# Netzteil_CA1.net
KiCad netlist of a schematic drawn in EAGLE
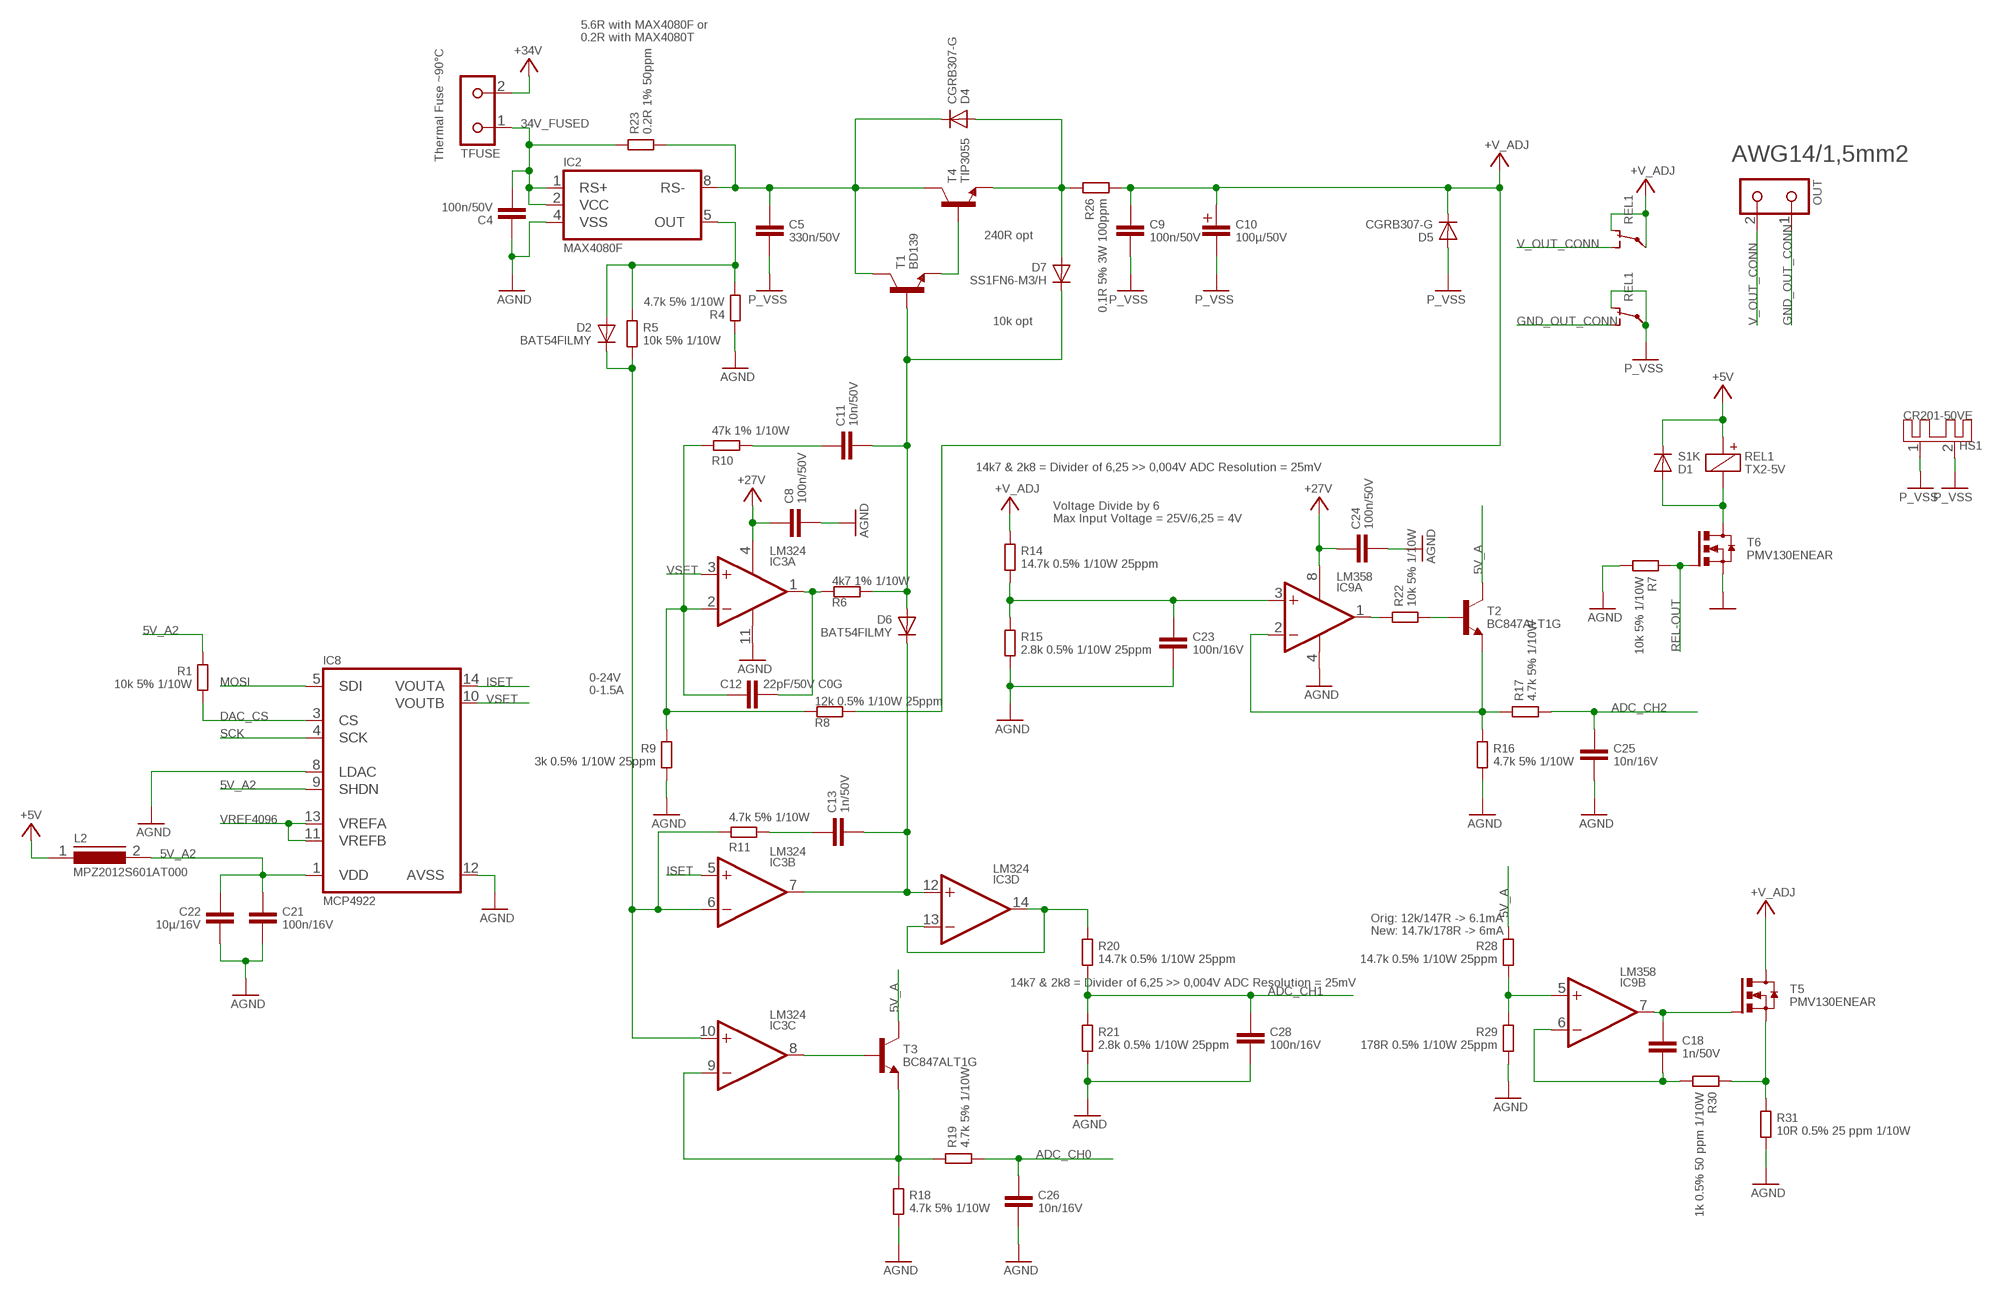
[diagram p0: schematic, sheet 1]
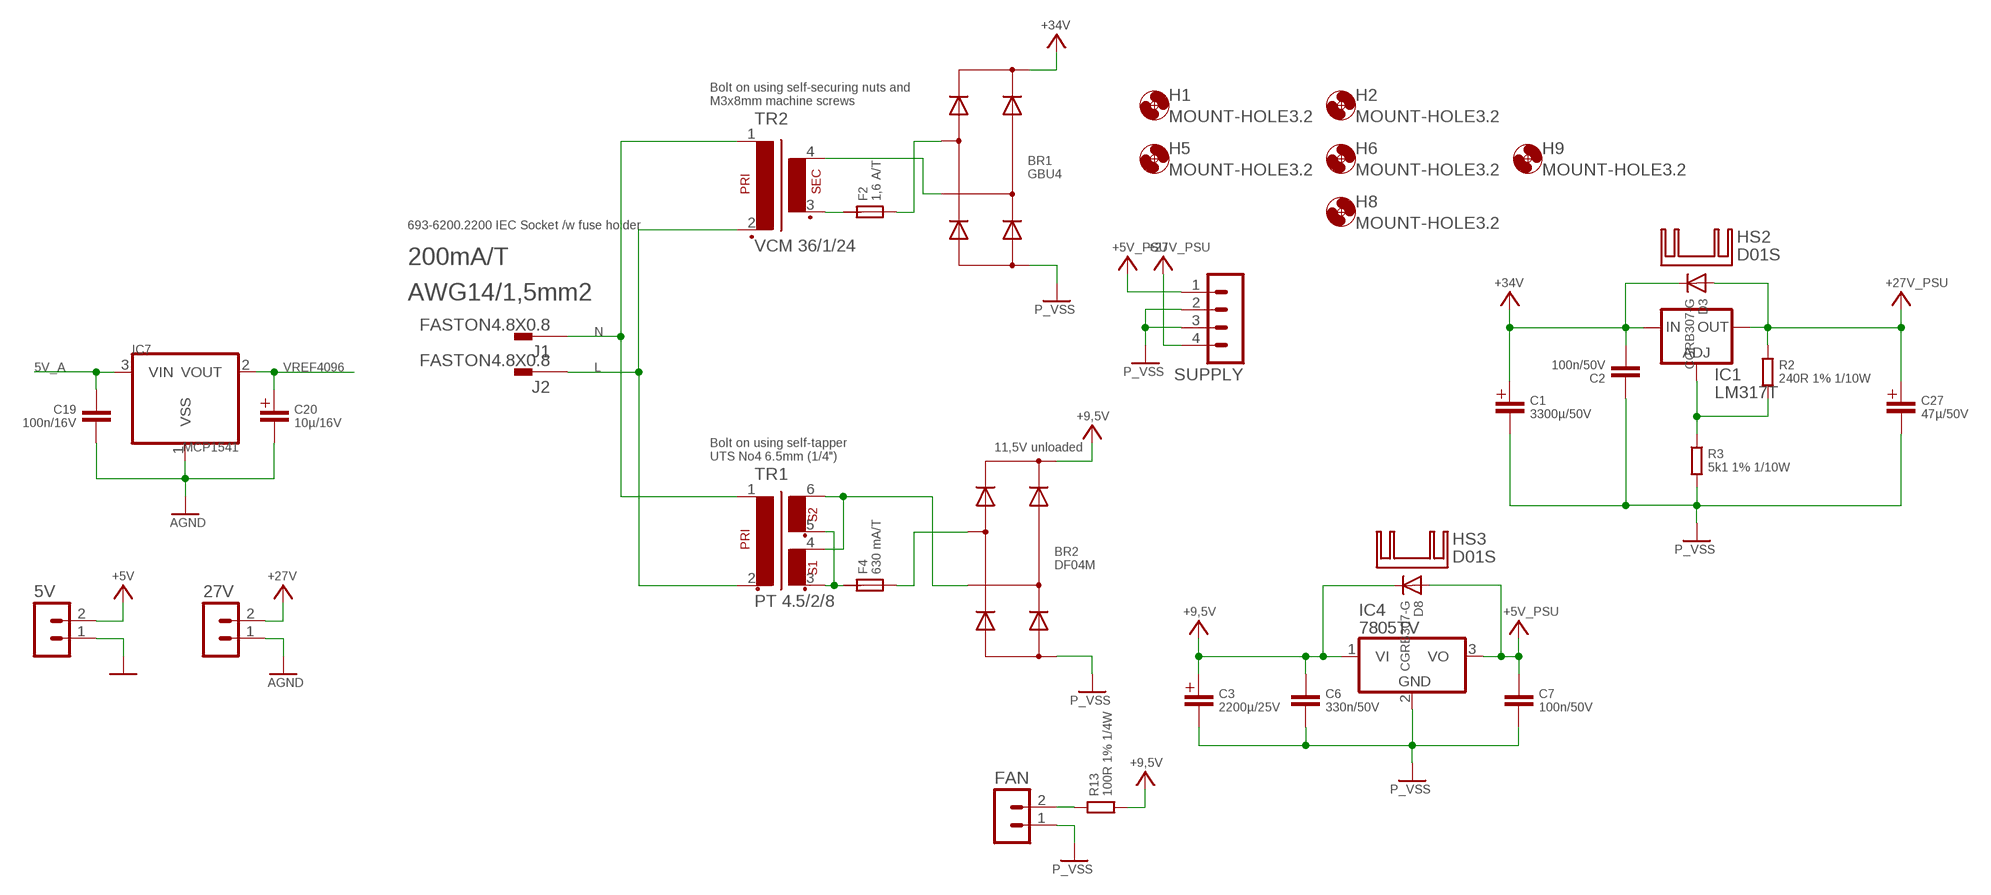
[diagram p1: schematic, sheet 2]
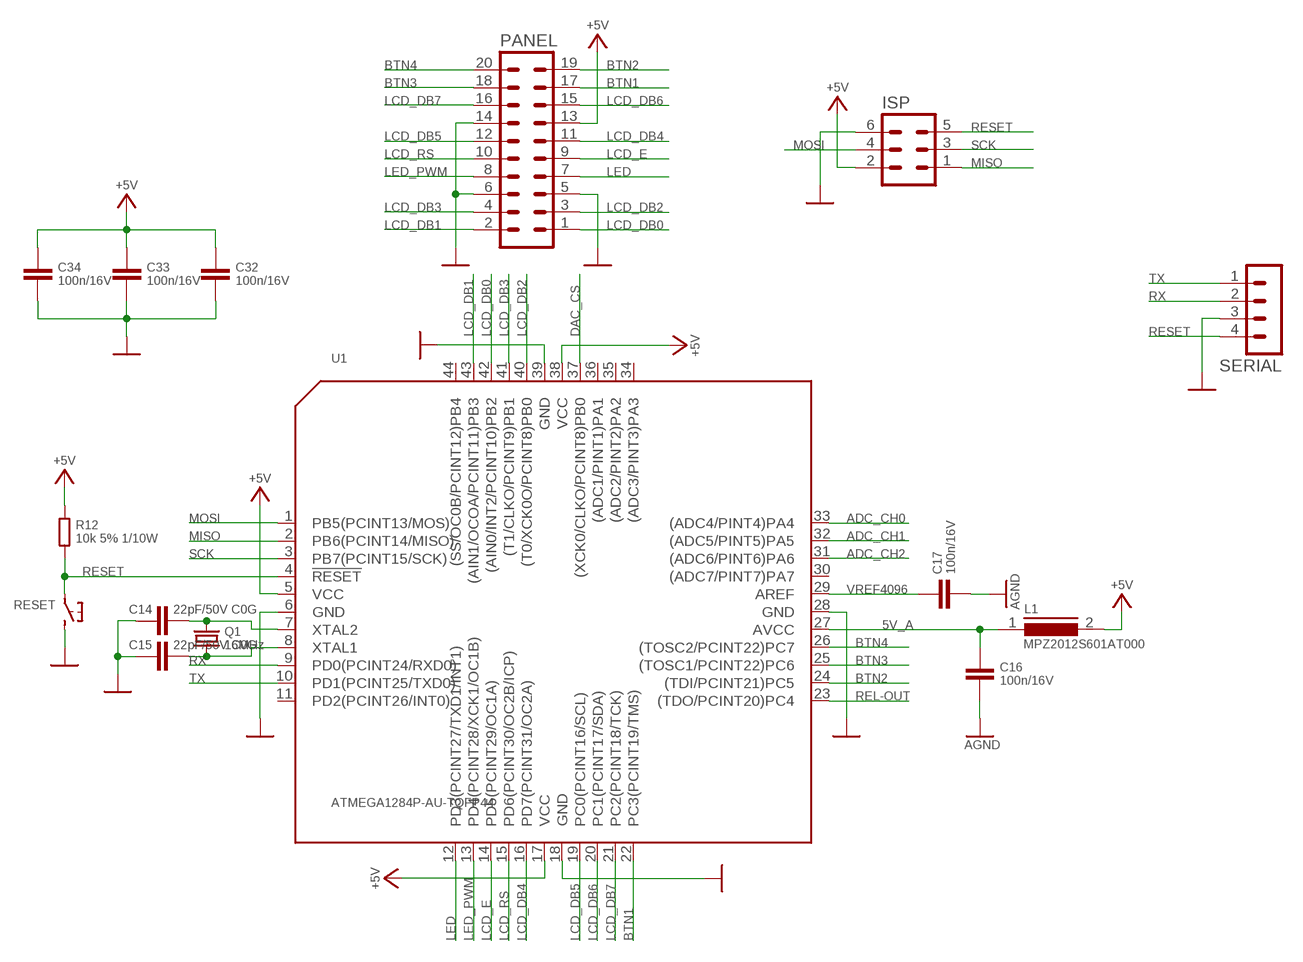
[diagram p2: schematic, sheet 3]

(export (version "E")
  (design (tool "Eeschema 10.0.6"))
  (components
    (comp (ref "C14")
      (value "22pF/50V C0G")
      (footprint "eagle-import:0805")
      (libsource (lib "eagle-import") (part "CC/0805"))
    )
    (comp (ref "C15")
      (value "22pF/50V C0G")
      (footprint "eagle-import:0805")
      (libsource (lib "eagle-import") (part "CC/0805"))
    )
    (comp (ref "C16")
      (value "100n/16V")
      (footprint "eagle-import:0805")
      (libsource (lib "eagle-import") (part "CC/0805"))
    )
    (comp (ref "C17")
      (value "100n/16V")
      (footprint "eagle-import:0805")
      (libsource (lib "eagle-import") (part "CC/0805"))
    )
    (comp (ref "C32")
      (value "100n/16V")
      (footprint "eagle-import:0805")
      (libsource (lib "eagle-import") (part "CC/0805"))
    )
    (comp (ref "C33")
      (value "100n/16V")
      (footprint "eagle-import:0805")
      (libsource (lib "eagle-import") (part "CC/0805"))
    )
    (comp (ref "C34")
      (value "100n/16V")
      (footprint "eagle-import:0805")
      (libsource (lib "eagle-import") (part "CC/0805"))
    )
    (comp (ref "ISP")
      (value "ML6")
      (footprint "eagle-import:ML6")
      (libsource (lib "eagle-import") (part "ML6"))
    )
    (comp (ref "L1")
      (value "MPZ2012S601AT000")
      (footprint "eagle-import:C0805K")
      (libsource (lib "eagle-import") (part "L0805"))
    )
    (comp (ref "PANEL")
      (value "MA10-2")
      (footprint "eagle-import:MA10-2")
      (libsource (lib "eagle-import") (part "MA10-2"))
    )
    (comp (ref "Q1")
      (value "16MHz")
      (footprint "eagle-import:Q-5X3.2MM-TXC-7A.SERIES")
      (libsource (lib "eagle-import") (part "Q5X3.2MM-TXC-7A-SERIES"))
    )
    (comp (ref "R12")
      (value "10k 5% 1/10W")
      (footprint "eagle-import:C0805K")
      (libsource (lib "eagle-import") (part "R-SMD0805"))
    )
    (comp (ref "RESET")
      (value "TS1B3F-10XX")
      (footprint "eagle-import:B3F-10XX")
      (libsource (lib "eagle-import") (part "TS1B3F-10XX"))
    )
    (comp (ref "SERIAL")
      (value "MA04-1")
      (footprint "eagle-import:MA04-1")
      (libsource (lib "eagle-import") (part "MA04-1"))
    )
    (comp (ref "U1")
      (value "ATMEGA1284P-AU-TQFP44")
      (footprint "eagle-import:TQFP44-0.8-9.6X9.6MM")
      (fields (field (name "MPN") "ATMEGA1284P-AU"))
      (libsource (lib "eagle-import") (part "MCU-ATMEGA1284P-AU(TQFP44)"))
    )
    (comp (ref "C4")
      (value "100n/50V")
      (footprint "eagle-import:0805")
      (libsource (lib "eagle-import") (part "CC/0805"))
    )
    (comp (ref "C5")
      (value "330n/50V")
      (footprint "eagle-import:0805")
      (libsource (lib "eagle-import") (part "CC/0805"))
    )
    (comp (ref "C8")
      (value "100n/50V")
      (footprint "eagle-import:0805")
      (libsource (lib "eagle-import") (part "CC/0805"))
    )
    (comp (ref "C9")
      (value "100n/50V")
      (footprint "eagle-import:0805")
      (libsource (lib "eagle-import") (part "CC/0805"))
    )
    (comp (ref "C10")
      (value "100µ/50V")
      (footprint "eagle-import:C+_3.5_8")
      (libsource (lib "eagle-import") (part "C+3.5/8"))
    )
    (comp (ref "C11")
      (value "10n/50V")
      (footprint "eagle-import:0805")
      (libsource (lib "eagle-import") (part "CC/0805"))
    )
    (comp (ref "C12")
      (value "22pF/50V C0G")
      (footprint "eagle-import:0805")
      (libsource (lib "eagle-import") (part "CC/0805"))
    )
    (comp (ref "C13")
      (value "1n/50V")
      (footprint "eagle-import:0805")
      (libsource (lib "eagle-import") (part "CC/0805"))
    )
    (comp (ref "C18")
      (value "1n/50V")
      (footprint "eagle-import:0805")
      (libsource (lib "eagle-import") (part "CC/0805"))
    )
    (comp (ref "C21")
      (value "100n/16V")
      (footprint "eagle-import:0805")
      (libsource (lib "eagle-import") (part "CC/0805"))
    )
    (comp (ref "C22")
      (value "10µ/16V")
      (footprint "eagle-import:1206")
      (libsource (lib "eagle-import") (part "CC/1206"))
    )
    (comp (ref "C23")
      (value "100n/16V")
      (footprint "eagle-import:0805")
      (libsource (lib "eagle-import") (part "CC/0805"))
    )
    (comp (ref "C24")
      (value "100n/50V")
      (footprint "eagle-import:0805")
      (libsource (lib "eagle-import") (part "CC/0805"))
    )
    (comp (ref "C25")
      (value "10n/16V")
      (footprint "eagle-import:0805")
      (libsource (lib "eagle-import") (part "CC/0805"))
    )
    (comp (ref "C26")
      (value "10n/16V")
      (footprint "eagle-import:0805")
      (libsource (lib "eagle-import") (part "CC/0805"))
    )
    (comp (ref "C28")
      (value "100n/16V")
      (footprint "eagle-import:0805")
      (libsource (lib "eagle-import") (part "CC/0805"))
    )
    (comp (ref "D1")
      (value "S1K")
      (footprint "eagle-import:DO214AC")
      (libsource (lib "eagle-import") (part "D"))
    )
    (comp (ref "D2")
      (value "BAT54FILMY")
      (footprint "eagle-import:SOT23")
      (libsource (lib "eagle-import") (part "DBAT54FILMY"))
    )
    (comp (ref "D4")
      (value "CGRB307-G")
      (footprint "eagle-import:DO214AA-CGRB307-G")
      (libsource (lib "eagle-import") (part "DWIDE"))
    )
    (comp (ref "D5")
      (value "CGRB307-G")
      (footprint "eagle-import:DO214AA-CGRB307-G")
      (libsource (lib "eagle-import") (part "DWIDE"))
    )
    (comp (ref "D6")
      (value "BAT54FILMY")
      (footprint "eagle-import:SOT23")
      (libsource (lib "eagle-import") (part "DBAT54FILMY"))
    )
    (comp (ref "D7")
      (value "SS1FN6-M3/H")
      (footprint "eagle-import:DO219AB-2")
      (libsource (lib "eagle-import") (part "DDO219AB-2"))
    )
    (comp (ref "HS1")
      (value "CR201-50VE")
      (footprint "eagle-import:CR201-50")
      (libsource (lib "eagle-import") (part "HSCR201-50"))
    )
    (comp (ref "IC2")
      (value "MAX4080F")
      (footprint "eagle-import:SOP8")
      (libsource (lib "eagle-import") (part "MAX4080"))
    )
    (comp (ref "IC3")
      (value "LM324")
      (footprint "eagle-import:SO14")
      (fields (field (name "OC_MOUSER") "595-LM324ADR"))
      (libsource (lib "eagle-import") (part "QUAD-OPVOPA4197"))
    )
    (comp (ref "IC8")
      (value "MCP4922")
      (footprint "eagle-import:TSSOP14")
      (libsource (lib "eagle-import") (part "MCP4922"))
    )
    (comp (ref "IC9")
      (value "LM358")
      (footprint "eagle-import:SOP8")
      (fields (field (name "OC_MOUSER") "595-LM358ADR"))
      (libsource (lib "eagle-import") (part "DUAL-OPVSOP8"))
    )
    (comp (ref "L2")
      (value "MPZ2012S601AT000")
      (footprint "eagle-import:C0805K")
      (libsource (lib "eagle-import") (part "L0805"))
    )
    (comp (ref "OUT")
      (value "KL2691311500002")
      (footprint "eagle-import:KL2-691311500002")
      (libsource (lib "eagle-import") (part "KL2691311500002"))
    )
    (comp (ref "R1")
      (value "10k 5% 1/10W")
      (footprint "eagle-import:C0805K")
      (libsource (lib "eagle-import") (part "R-SMD0805"))
    )
    (comp (ref "R4")
      (value "4.7k 5% 1/10W")
      (footprint "eagle-import:C0805K")
      (libsource (lib "eagle-import") (part "R-SMD0805"))
    )
    (comp (ref "R5")
      (value "10k 5% 1/10W")
      (footprint "eagle-import:C0805K")
      (libsource (lib "eagle-import") (part "R-SMD0805"))
    )
    (comp (ref "R6")
      (value "4k7 1% 1/10W")
      (footprint "eagle-import:C0805K")
      (libsource (lib "eagle-import") (part "R-SMD0805"))
    )
    (comp (ref "R7")
      (value "10k 5% 1/10W")
      (footprint "eagle-import:C0805K")
      (libsource (lib "eagle-import") (part "R-SMD0805"))
    )
    (comp (ref "R8")
      (value "12k 0.5% 1/10W 25ppm")
      (footprint "eagle-import:C0805K")
      (libsource (lib "eagle-import") (part "R-SMD0805"))
    )
    (comp (ref "R9")
      (value "3k 0.5% 1/10W 25ppm")
      (footprint "eagle-import:C0805K")
      (libsource (lib "eagle-import") (part "R-SMD0805"))
    )
    (comp (ref "R10")
      (value "47k 1% 1/10W")
      (footprint "eagle-import:C0805K")
      (libsource (lib "eagle-import") (part "R-SMD0805"))
    )
    (comp (ref "R11")
      (value "4.7k 5% 1/10W")
      (footprint "eagle-import:C0805K")
      (libsource (lib "eagle-import") (part "R-SMD0805"))
    )
    (comp (ref "R14")
      (value "14.7k 0.5% 1/10W 25ppm")
      (footprint "eagle-import:C0805K")
      (libsource (lib "eagle-import") (part "R-SMD0805"))
    )
    (comp (ref "R15")
      (value "2.8k 0.5% 1/10W 25ppm")
      (footprint "eagle-import:C0805K")
      (libsource (lib "eagle-import") (part "R-SMD0805"))
    )
    (comp (ref "R16")
      (value "4.7k 5% 1/10W")
      (footprint "eagle-import:C0805K")
      (libsource (lib "eagle-import") (part "R-SMD0805"))
    )
    (comp (ref "R17")
      (value "4.7k 5% 1/10W")
      (footprint "eagle-import:C0805K")
      (libsource (lib "eagle-import") (part "R-SMD0805"))
    )
    (comp (ref "R18")
      (value "4.7k 5% 1/10W")
      (footprint "eagle-import:C0805K")
      (libsource (lib "eagle-import") (part "R-SMD0805"))
    )
    (comp (ref "R19")
      (value "4.7k 5% 1/10W")
      (footprint "eagle-import:C0805K")
      (libsource (lib "eagle-import") (part "R-SMD0805"))
    )
    (comp (ref "R20")
      (value "14.7k 0.5% 1/10W 25ppm")
      (footprint "eagle-import:C0805K")
      (libsource (lib "eagle-import") (part "R-SMD0805"))
    )
    (comp (ref "R21")
      (value "2.8k 0.5% 1/10W 25ppm")
      (footprint "eagle-import:C0805K")
      (libsource (lib "eagle-import") (part "R-SMD0805"))
    )
    (comp (ref "R22")
      (value "10k 5% 1/10W")
      (footprint "eagle-import:C0805K")
      (libsource (lib "eagle-import") (part "R-SMD0805"))
    )
    (comp (ref "R23")
      (value "0.2R 1% 50ppm")
      (footprint "eagle-import:LRMAP2512")
      (libsource (lib "eagle-import") (part "R-SMDLRMAP2512"))
    )
    (comp (ref "R26")
      (value "0.1R 5% 3W 100ppm")
      (footprint "eagle-import:YAG_PT2512")
      (libsource (lib "eagle-import") (part "R-SMD2512"))
    )
    (comp (ref "R28")
      (value "14.7k 0.5% 1/10W 25ppm")
      (footprint "eagle-import:C0805K")
      (libsource (lib "eagle-import") (part "R-SMD0805"))
    )
    (comp (ref "R29")
      (value "178R 0.5% 1/10W 25ppm")
      (footprint "eagle-import:C0805K")
      (libsource (lib "eagle-import") (part "R-SMD0805"))
    )
    (comp (ref "R30")
      (value "1k 0.5% 50 ppm 1/10W")
      (footprint "eagle-import:C0805K")
      (libsource (lib "eagle-import") (part "R-SMD0805"))
    )
    (comp (ref "R31")
      (value "10R 0.5% 25 ppm 1/10W")
      (footprint "eagle-import:C0805K")
      (libsource (lib "eagle-import") (part "R-SMD0805"))
    )
    (comp (ref "REL1")
      (value "TX2-5V")
      (footprint "eagle-import:REL-TX2")
      (fields (field (name "OC_MOUSER") "769-TX2-5V"))
      (libsource (lib "eagle-import") (part "REL-2UTX2"))
    )
    (comp (ref "T1")
      (value "BD139")
      (footprint "eagle-import:TO126")
      (libsource (lib "eagle-import") (part "T-NPNTO126-ECB"))
    )
    (comp (ref "T2")
      (value "BC847ALT1G")
      (footprint "eagle-import:SOT23-BEC")
      (libsource (lib "eagle-import") (part "T-NPNSOT23-BEC"))
    )
    (comp (ref "T3")
      (value "BC847ALT1G")
      (footprint "eagle-import:SOT23-BEC")
      (libsource (lib "eagle-import") (part "T-NPNSOT23-BEC"))
    )
    (comp (ref "T4")
      (value "TIP3055")
      (footprint "eagle-import:TOP3AV")
      (libsource (lib "eagle-import") (part "T-NPNTOP3AV-BCE"))
    )
    (comp (ref "T5")
      (value "PMV130ENEAR")
      (footprint "eagle-import:SOT23")
      (libsource (lib "eagle-import") (part "T-NMOSIRLML2502PBF"))
    )
    (comp (ref "T6")
      (value "PMV130ENEAR")
      (footprint "eagle-import:SOT23")
      (libsource (lib "eagle-import") (part "T-NMOSIRLML2502PBF"))
    )
    (comp (ref "TFUSE")
      (value "KL2691311500002")
      (footprint "eagle-import:KL2-691311500002")
      (libsource (lib "eagle-import") (part "KL2691311500002"))
    )
    (comp (ref "5V")
      (value "JST-PH-2.0-2P")
      (footprint "eagle-import:JST-PH-2.0-2P")
      (libsource (lib "eagle-import") (part "JST-PH-2.0-2P"))
    )
    (comp (ref "27V")
      (value "JST-PH-2.0-2P")
      (footprint "eagle-import:JST-PH-2.0-2P")
      (libsource (lib "eagle-import") (part "JST-PH-2.0-2P"))
    )
    (comp (ref "BR1")
      (value "GBU4")
      (footprint "eagle-import:GBU4S")
      (libsource (lib "eagle-import") (part "GBU8M"))
    )
    (comp (ref "BR2")
      (value "DF04M")
      (footprint "eagle-import:BR-DIL2")
      (libsource (lib "eagle-import") (part "BRDIL2"))
    )
    (comp (ref "C1")
      (value "3300µ/50V")
      (footprint "eagle-import:C+_7.5_18")
      (libsource (lib "eagle-import") (part "C+7.5/18"))
    )
    (comp (ref "C2")
      (value "100n/50V")
      (footprint "eagle-import:0805")
      (libsource (lib "eagle-import") (part "CC/0805"))
    )
    (comp (ref "C3")
      (value "2200µ/25V")
      (footprint "eagle-import:C+_5_12.5")
      (libsource (lib "eagle-import") (part "C+5/12.5"))
    )
    (comp (ref "C6")
      (value "330n/50V")
      (footprint "eagle-import:0805")
      (libsource (lib "eagle-import") (part "CC/0805"))
    )
    (comp (ref "C7")
      (value "100n/50V")
      (footprint "eagle-import:0805")
      (libsource (lib "eagle-import") (part "CC/0805"))
    )
    (comp (ref "C19")
      (value "100n/16V")
      (footprint "eagle-import:0805")
      (libsource (lib "eagle-import") (part "CC/0805"))
    )
    (comp (ref "C20")
      (value "10µ/16V")
      (footprint "eagle-import:C+_1.5_4")
      (libsource (lib "eagle-import") (part "C+1.5/4"))
    )
    (comp (ref "C27")
      (value "47µ/50V")
      (footprint "eagle-import:C+_2.5_6.3")
      (libsource (lib "eagle-import") (part "C+2.5/6.3"))
    )
    (comp (ref "D3")
      (value "CGRB307-G")
      (footprint "eagle-import:DO214AA-CGRB307-G")
      (libsource (lib "eagle-import") (part "DWIDE"))
    )
    (comp (ref "D8")
      (value "CGRB307-G")
      (footprint "eagle-import:DO214AA-CGRB307-G")
      (libsource (lib "eagle-import") (part "DWIDE"))
    )
    (comp (ref "F2")
      (value "1,6 A/T")
      (footprint "eagle-import:F5X20")
      (libsource (lib "eagle-import") (part "F5X20"))
    )
    (comp (ref "F4")
      (value "630 mA/T")
      (footprint "eagle-import:F5X20")
      (libsource (lib "eagle-import") (part "F5X20"))
    )
    (comp (ref "FAN")
      (value "JST-PH-2.0-2P")
      (footprint "eagle-import:JST-PH-2.0-2P")
      (libsource (lib "eagle-import") (part "JST-PH-2.0-2P"))
    )
    (comp (ref "H1")
      (value "MOUNT-HOLE3.2")
      (footprint "eagle-import:3,2")
      (libsource (lib "eagle-import") (part "MOUNT-HOLE3.2"))
    )
    (comp (ref "H2")
      (value "MOUNT-HOLE3.2")
      (footprint "eagle-import:3,2")
      (libsource (lib "eagle-import") (part "MOUNT-HOLE3.2"))
    )
    (comp (ref "H5")
      (value "MOUNT-HOLE3.2")
      (footprint "eagle-import:3,2")
      (libsource (lib "eagle-import") (part "MOUNT-HOLE3.2"))
    )
    (comp (ref "H6")
      (value "MOUNT-HOLE3.2")
      (footprint "eagle-import:3,2")
      (libsource (lib "eagle-import") (part "MOUNT-HOLE3.2"))
    )
    (comp (ref "H8")
      (value "MOUNT-HOLE3.2")
      (footprint "eagle-import:3,2")
      (libsource (lib "eagle-import") (part "MOUNT-HOLE3.2"))
    )
    (comp (ref "H9")
      (value "MOUNT-HOLE3.2")
      (footprint "eagle-import:3,2")
      (libsource (lib "eagle-import") (part "MOUNT-HOLE3.2"))
    )
    (comp (ref "HS2")
      (value "D01S")
      (footprint "eagle-import:D01S")
      (libsource (lib "eagle-import") (part "D01S"))
    )
    (comp (ref "HS3")
      (value "D01S")
      (footprint "eagle-import:D01S")
      (libsource (lib "eagle-import") (part "D01S"))
    )
    (comp (ref "IC1")
      (value "LM317T")
      (footprint "eagle-import:317TS")
      (libsource (lib "eagle-import") (part "LM317TS"))
    )
    (comp (ref "IC4")
      (value "7805TV")
      (footprint "eagle-import:TO220V")
      (libsource (lib "eagle-import") (part "78TV05"))
    )
    (comp (ref "IC7")
      (value "MCP1541")
      (footprint "eagle-import:TO92-G")
      (libsource (lib "eagle-import") (part "MCP1541"))
    )
    (comp (ref "J1")
      (value "FASTON4.8X0.8")
      (footprint "eagle-import:FASTON-4.8X0.8")
      (libsource (lib "eagle-import") (part "FASTON4.8X0.8"))
    )
    (comp (ref "J2")
      (value "FASTON4.8X0.8")
      (footprint "eagle-import:FASTON-4.8X0.8")
      (libsource (lib "eagle-import") (part "FASTON4.8X0.8"))
    )
    (comp (ref "R2")
      (value "240R 1% 1/10W")
      (footprint "eagle-import:C0805K")
      (libsource (lib "eagle-import") (part "R-SMD0805"))
    )
    (comp (ref "R3")
      (value "5k1 1% 1/10W")
      (footprint "eagle-import:C0805K")
      (libsource (lib "eagle-import") (part "R-SMD0805"))
    )
    (comp (ref "R13")
      (value "100R 1% 1/4W")
      (footprint "eagle-import:C0805K")
      (libsource (lib "eagle-import") (part "R-SMD0805"))
    )
    (comp (ref "SUPPLY")
      (value "JST-PH-2.0-4P")
      (footprint "eagle-import:JST-PH-2.0-4P")
      (libsource (lib "eagle-import") (part "JST-PH-2.0-4P"))
    )
    (comp (ref "TR1")
      (value "PT 4.5/2/8")
      (footprint "eagle-import:PT_4,5_2_..")
      (libsource (lib "eagle-import") (part "PT4,5/2/.."))
    )
    (comp (ref "TR2")
      (value "VCM 36/1/24")
      (footprint "eagle-import:VCM36_1_24")
      (libsource (lib "eagle-import") (part "VCM36/1/24"))
    )
  )
  (nets
    (net (code "1") (name "+5V") (class "Default")
      (node (ref "5V") (pin "2") (pinfunction "2_2") (pintype "passive"))
      (node (ref "C32") (pin "1") (pinfunction "1_1") (pintype "passive"))
      (node (ref "C33") (pin "1") (pinfunction "1_1") (pintype "passive"))
      (node (ref "C34") (pin "1") (pinfunction "1_1") (pintype "passive"))
      (node (ref "D1") (pin "C") (pinfunction "C_C") (pintype "passive"))
      (node (ref "ISP") (pin "2") (pinfunction "2_2") (pintype "passive"))
      (node (ref "L1") (pin "2") (pinfunction "2_2") (pintype "passive"))
      (node (ref "L2") (pin "1") (pinfunction "1_1") (pintype "passive"))
      (node (ref "PANEL") (pin "13") (pinfunction "13_13") (pintype "passive"))
      (node (ref "R12") (pin "1") (pinfunction "1_1") (pintype "passive"))
      (node (ref "REL1") (pin "+") (pinfunction "+_+") (pintype "passive"))
      (node (ref "U1") (pin "17") (pinfunction "VCC_17") (pintype "bidirectional"))
      (node (ref "U1") (pin "38") (pinfunction "VCC_38") (pintype "bidirectional"))
      (node (ref "U1") (pin "5") (pinfunction "VCC_5") (pintype "bidirectional"))
    )
    (net (code "2") (name "+5V_PSU") (class "Default")
      (node (ref "C7") (pin "1") (pinfunction "1_1") (pintype "passive"))
      (node (ref "D8") (pin "A") (pinfunction "A_A") (pintype "passive"))
      (node (ref "IC4") (pin "3") (pinfunction "VO_3") (pintype "passive"))
      (node (ref "SUPPLY") (pin "1") (pinfunction "1_1") (pintype "passive"))
    )
    (net (code "3") (name "+9,5V") (class "Default")
      (node (ref "BR2") (pin "DC+") (pinfunction "DC+_DC+") (pintype "passive"))
      (node (ref "C3") (pin "+") (pinfunction "+_+") (pintype "passive"))
      (node (ref "C6") (pin "1") (pinfunction "1_1") (pintype "passive"))
      (node (ref "D8") (pin "C") (pinfunction "C_C") (pintype "passive"))
      (node (ref "IC4") (pin "1") (pinfunction "VI_1") (pintype "input"))
      (node (ref "R13") (pin "2") (pinfunction "2_2") (pintype "passive"))
    )
    (net (code "4") (name "+27V") (class "Default")
      (node (ref "27V") (pin "2") (pinfunction "2_2") (pintype "passive"))
      (node (ref "C24") (pin "1") (pinfunction "1_1") (pintype "passive"))
      (node (ref "C8") (pin "1") (pinfunction "1_1") (pintype "passive"))
      (node (ref "IC3") (pin "4") (pinfunction "V+_4") (pintype "power_in"))
      (node (ref "IC9") (pin "8") (pinfunction "V+_8") (pintype "power_in"))
    )
    (net (code "5") (name "+27V_PSU") (class "Default")
      (node (ref "C27") (pin "+") (pinfunction "+_+") (pintype "passive"))
      (node (ref "D3") (pin "A") (pinfunction "A_A") (pintype "passive"))
      (node (ref "IC1") (pin "2") (pinfunction "OUT_2") (pintype "passive"))
      (node (ref "R2") (pin "1") (pinfunction "1_1") (pintype "passive"))
      (node (ref "SUPPLY") (pin "4") (pinfunction "4_4") (pintype "passive"))
    )
    (net (code "6") (name "+34V") (class "Default")
      (node (ref "BR1") (pin "+") (pinfunction "DC+_+") (pintype "passive"))
      (node (ref "C1") (pin "+") (pinfunction "+_+") (pintype "passive"))
      (node (ref "C2") (pin "2") (pinfunction "2_2") (pintype "passive"))
      (node (ref "D3") (pin "C") (pinfunction "C_C") (pintype "passive"))
      (node (ref "IC1") (pin "3") (pinfunction "IN_3") (pintype "input"))
      (node (ref "TFUSE") (pin "2") (pinfunction "2_2") (pintype "passive"))
    )
    (net (code "7") (name "+V_ADJ") (class "Default")
      (node (ref "C10") (pin "+") (pinfunction "+_+") (pintype "passive"))
      (node (ref "C9") (pin "1") (pinfunction "1_1") (pintype "passive"))
      (node (ref "D5") (pin "C") (pinfunction "C_C") (pintype "passive"))
      (node (ref "R14") (pin "1") (pinfunction "1_1") (pintype "passive"))
      (node (ref "R26") (pin "2") (pinfunction "2_2") (pintype "passive"))
      (node (ref "R8") (pin "1") (pinfunction "1_1") (pintype "passive"))
      (node (ref "REL1") (pin "O1") (pinfunction "O_O1") (pintype "passive"))
      (node (ref "REL1") (pin "P1") (pinfunction "P_P1") (pintype "passive"))
      (node (ref "T5") (pin "3") (pinfunction "D_3") (pintype "passive"))
    )
    (net (code "8") (name "5V_A") (class "Default")
      (node (ref "C16") (pin "1") (pinfunction "1_1") (pintype "passive"))
      (node (ref "C19") (pin "1") (pinfunction "1_1") (pintype "passive"))
      (node (ref "IC7") (pin "3") (pinfunction "VIN_3") (pintype "power_in"))
      (node (ref "L1") (pin "1") (pinfunction "1_1") (pintype "passive"))
      (node (ref "R28") (pin "1") (pinfunction "1_1") (pintype "passive"))
      (node (ref "T2") (pin "C") (pinfunction "C_C") (pintype "passive"))
      (node (ref "T3") (pin "C") (pinfunction "C_C") (pintype "passive"))
      (node (ref "U1") (pin "27") (pinfunction "AVCC_27") (pintype "bidirectional"))
    )
    (net (code "9") (name "5V_A2") (class "Default")
      (node (ref "C21") (pin "1") (pinfunction "1_1") (pintype "passive"))
      (node (ref "C22") (pin "1") (pinfunction "1_1") (pintype "passive"))
      (node (ref "IC8") (pin "1") (pinfunction "VDD_1") (pintype "power_in"))
      (node (ref "IC8") (pin "9") (pinfunction "SHDN_9") (pintype "input"))
      (node (ref "L2") (pin "2") (pinfunction "2_2") (pintype "passive"))
      (node (ref "R1") (pin "1") (pinfunction "1_1") (pintype "passive"))
    )
    (net (code "10") (name "34V_FUSED") (class "Default")
      (node (ref "C4") (pin "2") (pinfunction "2_2") (pintype "passive"))
      (node (ref "IC2") (pin "1") (pinfunction "RS+_1") (pintype "input"))
      (node (ref "IC2") (pin "2") (pinfunction "VCC_2") (pintype "power_in"))
      (node (ref "R23") (pin "1") (pinfunction "1_1") (pintype "passive"))
      (node (ref "TFUSE") (pin "1") (pinfunction "1_1") (pintype "passive"))
    )
    (net (code "11") (name "ADC_CH0") (class "Default")
      (node (ref "C26") (pin "1") (pinfunction "1_1") (pintype "passive"))
      (node (ref "R19") (pin "2") (pinfunction "2_2") (pintype "passive"))
      (node (ref "U1") (pin "33") (pinfunction "(ADC4/PINT4)PA4_33") (pintype "bidirectional"))
    )
    (net (code "12") (name "ADC_CH1") (class "Default")
      (node (ref "C28") (pin "1") (pinfunction "1_1") (pintype "passive"))
      (node (ref "R20") (pin "2") (pinfunction "2_2") (pintype "passive"))
      (node (ref "R21") (pin "1") (pinfunction "1_1") (pintype "passive"))
      (node (ref "U1") (pin "32") (pinfunction "(ADC5/PINT5)PA5_32") (pintype "bidirectional"))
    )
    (net (code "13") (name "ADC_CH2") (class "Default")
      (node (ref "C25") (pin "1") (pinfunction "1_1") (pintype "passive"))
      (node (ref "R17") (pin "2") (pinfunction "2_2") (pintype "passive"))
      (node (ref "U1") (pin "31") (pinfunction "(ADC6/PINT6)PA6_31") (pintype "bidirectional"))
    )
    (net (code "14") (name "AGND") (class "Default")
      (node (ref "27V") (pin "1") (pinfunction "1_1") (pintype "passive"))
      (node (ref "C16") (pin "2") (pinfunction "2_2") (pintype "passive"))
      (node (ref "C17") (pin "2") (pinfunction "2_2") (pintype "passive"))
      (node (ref "C19") (pin "2") (pinfunction "2_2") (pintype "passive"))
      (node (ref "C20") (pin "-") (pinfunction "-_-") (pintype "passive"))
      (node (ref "C21") (pin "2") (pinfunction "2_2") (pintype "passive"))
      (node (ref "C22") (pin "2") (pinfunction "2_2") (pintype "passive"))
      (node (ref "C23") (pin "2") (pinfunction "2_2") (pintype "passive"))
      (node (ref "C24") (pin "2") (pinfunction "2_2") (pintype "passive"))
      (node (ref "C25") (pin "2") (pinfunction "2_2") (pintype "passive"))
      (node (ref "C26") (pin "2") (pinfunction "2_2") (pintype "passive"))
      (node (ref "C28") (pin "2") (pinfunction "2_2") (pintype "passive"))
      (node (ref "C4") (pin "1") (pinfunction "1_1") (pintype "passive"))
      (node (ref "C8") (pin "2") (pinfunction "2_2") (pintype "passive"))
      (node (ref "IC2") (pin "4") (pinfunction "VSS_4") (pintype "power_in"))
      (node (ref "IC3") (pin "11") (pinfunction "V-_11") (pintype "power_in"))
      (node (ref "IC7") (pin "1") (pinfunction "VSS_1") (pintype "power_in"))
      (node (ref "IC8") (pin "12") (pinfunction "AVSS_12") (pintype "power_in"))
      (node (ref "IC8") (pin "8") (pinfunction "LDAC_8") (pintype "input"))
      (node (ref "IC9") (pin "4") (pinfunction "V-_4") (pintype "power_in"))
      (node (ref "R15") (pin "2") (pinfunction "2_2") (pintype "passive"))
      (node (ref "R16") (pin "2") (pinfunction "2_2") (pintype "passive"))
      (node (ref "R18") (pin "2") (pinfunction "2_2") (pintype "passive"))
      (node (ref "R21") (pin "2") (pinfunction "2_2") (pintype "passive"))
      (node (ref "R29") (pin "2") (pinfunction "2_2") (pintype "passive"))
      (node (ref "R31") (pin "2") (pinfunction "2_2") (pintype "passive"))
      (node (ref "R4") (pin "1") (pinfunction "1_1") (pintype "passive"))
      (node (ref "R7") (pin "2") (pinfunction "2_2") (pintype "passive"))
      (node (ref "R9") (pin "2") (pinfunction "2_2") (pintype "passive"))
    )
    (net (code "15") (name "BTN1") (class "Default")
      (node (ref "PANEL") (pin "17") (pinfunction "17_17") (pintype "passive"))
      (node (ref "U1") (pin "22") (pinfunction "PC3(PCINT19/TMS)_22") (pintype "bidirectional"))
    )
    (net (code "16") (name "BTN2") (class "Default")
      (node (ref "PANEL") (pin "19") (pinfunction "19_19") (pintype "passive"))
      (node (ref "U1") (pin "24") (pinfunction "(TDI/PCINT21)PC5_24") (pintype "bidirectional"))
    )
    (net (code "17") (name "BTN3") (class "Default")
      (node (ref "PANEL") (pin "18") (pinfunction "18_18") (pintype "passive"))
      (node (ref "U1") (pin "25") (pinfunction "(TOSC1/PCINT22)PC6_25") (pintype "bidirectional"))
    )
    (net (code "18") (name "BTN4") (class "Default")
      (node (ref "PANEL") (pin "20") (pinfunction "20_20") (pintype "passive"))
      (node (ref "U1") (pin "26") (pinfunction "(TOSC2/PCINT22)PC7_26") (pintype "bidirectional"))
    )
    (net (code "19") (name "DAC_CS") (class "Default")
      (node (ref "IC8") (pin "3") (pinfunction "CS_3") (pintype "input"))
      (node (ref "R1") (pin "2") (pinfunction "2_2") (pintype "passive"))
      (node (ref "U1") (pin "37") (pinfunction "(XCK0/CLKO/PCINT8)PB0_37") (pintype "bidirectional"))
    )
    (net (code "20") (name "GND_OUT_CONN") (class "Default")
      (node (ref "OUT") (pin "1") (pinfunction "1_1") (pintype "passive"))
      (node (ref "REL1") (pin "S2") (pinfunction "S_S2") (pintype "passive"))
    )
    (net (code "21") (name "ISET") (class "Default")
      (node (ref "IC3") (pin "5") (pinfunction "+IN_5") (pintype "input"))
      (node (ref "IC8") (pin "14") (pinfunction "VOUTA_14") (pintype "output"))
    )
    (net (code "22") (name "L") (class "Default")
      (node (ref "J2") (pin "A1") (pinfunction "1_A1") (pintype "passive"))
      (node (ref "J2") (pin "A2") (pinfunction "1_A2") (pintype "passive"))
      (node (ref "TR1") (pin "2") (pinfunction "2_2") (pintype "passive"))
      (node (ref "TR2") (pin "2") (pinfunction "P2_2") (pintype "passive"))
    )
    (net (code "23") (name "LCD_DB0") (class "Default")
      (node (ref "PANEL") (pin "1") (pinfunction "1_1") (pintype "passive"))
      (node (ref "U1") (pin "42") (pinfunction "(AIN0/INT2/PCINT10)PB2_42") (pintype "bidirectional"))
    )
    (net (code "24") (name "LCD_DB1") (class "Default")
      (node (ref "PANEL") (pin "2") (pinfunction "2_2") (pintype "passive"))
      (node (ref "U1") (pin "43") (pinfunction "(AIN1/OCOA/PCINT11)PB3_43") (pintype "bidirectional"))
    )
    (net (code "25") (name "LCD_DB2") (class "Default")
      (node (ref "PANEL") (pin "3") (pinfunction "3_3") (pintype "passive"))
      (node (ref "U1") (pin "40") (pinfunction "(T0/XCK0O/PCINT8)PB0_40") (pintype "bidirectional"))
    )
    (net (code "26") (name "LCD_DB3") (class "Default")
      (node (ref "PANEL") (pin "4") (pinfunction "4_4") (pintype "passive"))
      (node (ref "U1") (pin "41") (pinfunction "(T1/CLKO/PCINT9)PB1_41") (pintype "bidirectional"))
    )
    (net (code "27") (name "LCD_DB4") (class "Default")
      (node (ref "PANEL") (pin "11") (pinfunction "11_11") (pintype "passive"))
      (node (ref "U1") (pin "16") (pinfunction "PD7(PCINT31/OC2A)_16") (pintype "bidirectional"))
    )
    (net (code "28") (name "LCD_DB5") (class "Default")
      (node (ref "PANEL") (pin "12") (pinfunction "12_12") (pintype "passive"))
      (node (ref "U1") (pin "19") (pinfunction "PC0(PCINT16/SCL)_19") (pintype "bidirectional"))
    )
    (net (code "29") (name "LCD_DB6") (class "Default")
      (node (ref "PANEL") (pin "15") (pinfunction "15_15") (pintype "passive"))
      (node (ref "U1") (pin "20") (pinfunction "PC1(PCINT17/SDA)_20") (pintype "bidirectional"))
    )
    (net (code "30") (name "LCD_DB7") (class "Default")
      (node (ref "PANEL") (pin "16") (pinfunction "16_16") (pintype "passive"))
      (node (ref "U1") (pin "21") (pinfunction "PC2(PCINT18/TCK)_21") (pintype "bidirectional"))
    )
    (net (code "31") (name "LCD_E") (class "Default")
      (node (ref "PANEL") (pin "9") (pinfunction "9_9") (pintype "passive"))
      (node (ref "U1") (pin "14") (pinfunction "PD5(PCINT29/OC1A)_14") (pintype "bidirectional"))
    )
    (net (code "32") (name "LCD_RS") (class "Default")
      (node (ref "PANEL") (pin "10") (pinfunction "10_10") (pintype "passive"))
      (node (ref "U1") (pin "15") (pinfunction "PD6(PCINT30/OC2B/ICP)_15") (pintype "bidirectional"))
    )
    (net (code "33") (name "LED") (class "Default")
      (node (ref "PANEL") (pin "7") (pinfunction "7_7") (pintype "passive"))
      (node (ref "U1") (pin "12") (pinfunction "PD3(PCINT27/TXD1/INT1)_12") (pintype "bidirectional"))
    )
    (net (code "34") (name "LED_PWM") (class "Default")
      (node (ref "PANEL") (pin "8") (pinfunction "8_8") (pintype "passive"))
      (node (ref "U1") (pin "13") (pinfunction "PD4(PCINT28/XCK1/OC1B)_13") (pintype "bidirectional"))
    )
    (net (code "35") (name "MISO") (class "Default")
      (node (ref "ISP") (pin "1") (pinfunction "1_1") (pintype "passive"))
      (node (ref "U1") (pin "2") (pinfunction "PB6(PCINT14/MISO)_2") (pintype "bidirectional"))
    )
    (net (code "36") (name "MOSI") (class "Default")
      (node (ref "IC8") (pin "5") (pinfunction "SDI_5") (pintype "input"))
      (node (ref "ISP") (pin "4") (pinfunction "4_4") (pintype "passive"))
      (node (ref "U1") (pin "1") (pinfunction "PB5(PCINT13/MOS)_1") (pintype "bidirectional"))
    )
    (net (code "37") (name "N") (class "Default")
      (node (ref "J1") (pin "A1") (pinfunction "1_A1") (pintype "passive"))
      (node (ref "J1") (pin "A2") (pinfunction "1_A2") (pintype "passive"))
      (node (ref "TR1") (pin "1") (pinfunction "1_1") (pintype "passive"))
      (node (ref "TR2") (pin "1") (pinfunction "P1_1") (pintype "passive"))
    )
    (net (code "38") (name "Net-(BR1-PadAC1)") (class "Default")
      (node (ref "BR1") (pin "AC1") (pinfunction "AC1_AC1") (pintype "passive"))
      (node (ref "F2") (pin "3") (pinfunction "2_3") (pintype "passive"))
      (node (ref "F2") (pin "4") (pinfunction "2_4") (pintype "passive"))
    )
    (net (code "39") (name "Net-(BR2-PadAC1)") (class "Default")
      (node (ref "BR2") (pin "AC1") (pinfunction "AC1_AC1") (pintype "passive"))
      (node (ref "F4") (pin "3") (pinfunction "2_3") (pintype "passive"))
      (node (ref "F4") (pin "4") (pinfunction "2_4") (pintype "passive"))
    )
    (net (code "40") (name "Net-(BR2-PadAC2)") (class "Default")
      (node (ref "BR2") (pin "AC2") (pinfunction "AC2_AC2") (pintype "passive"))
      (node (ref "TR1") (pin "4") (pinfunction "4_4") (pintype "passive"))
      (node (ref "TR1") (pin "6") (pinfunction "6_6") (pintype "passive"))
    )
    (net (code "41") (name "Net-(C11-Pad1)") (class "Default")
      (node (ref "C11") (pin "1") (pinfunction "1_1") (pintype "passive"))
      (node (ref "R10") (pin "1") (pinfunction "1_1") (pintype "passive"))
    )
    (net (code "42") (name "Net-(C13-Pad1)") (class "Default")
      (node (ref "C13") (pin "1") (pinfunction "1_1") (pintype "passive"))
      (node (ref "R11") (pin "1") (pinfunction "1_1") (pintype "passive"))
    )
    (net (code "43") (name "Net-(D2-A)") (class "Default")
      (node (ref "D2") (pin "1") (pinfunction "A_1") (pintype "passive"))
      (node (ref "IC2") (pin "5") (pinfunction "OUT_5") (pintype "bidirectional"))
      (node (ref "R4") (pin "2") (pinfunction "2_2") (pintype "passive"))
      (node (ref "R5") (pin "1") (pinfunction "1_1") (pintype "passive"))
    )
    (net (code "44") (name "Net-(D2-C)") (class "Default")
      (node (ref "D2") (pin "3") (pinfunction "C_3") (pintype "passive"))
      (node (ref "IC3") (pin "10") (pinfunction "+IN_10") (pintype "input"))
      (node (ref "IC3") (pin "6") (pinfunction "-IN_6") (pintype "input"))
      (node (ref "R11") (pin "2") (pinfunction "2_2") (pintype "passive"))
      (node (ref "R5") (pin "2") (pinfunction "2_2") (pintype "passive"))
    )
    (net (code "45") (name "Net-(D4-PadA)") (class "Default")
      (node (ref "D4") (pin "A") (pinfunction "A_A") (pintype "passive"))
      (node (ref "D7") (pin "A") (pinfunction "A_A") (pintype "passive"))
      (node (ref "R26") (pin "1") (pinfunction "1_1") (pintype "passive"))
      (node (ref "T4") (pin "E") (pinfunction "E_E") (pintype "passive"))
    )
    (net (code "46") (name "Net-(D6-A)") (class "Default")
      (node (ref "C11") (pin "2") (pinfunction "2_2") (pintype "passive"))
      (node (ref "D6") (pin "1") (pinfunction "A_1") (pintype "passive"))
      (node (ref "D7") (pin "C") (pinfunction "C_C") (pintype "passive"))
      (node (ref "R6") (pin "1") (pinfunction "1_1") (pintype "passive"))
      (node (ref "T1") (pin "3") (pinfunction "B_3") (pintype "passive"))
    )
    (net (code "47") (name "Net-(D6-C)") (class "Default")
      (node (ref "C13") (pin "2") (pinfunction "2_2") (pintype "passive"))
      (node (ref "D6") (pin "3") (pinfunction "C_3") (pintype "passive"))
      (node (ref "IC3") (pin "12") (pinfunction "+IN_12") (pintype "input"))
      (node (ref "IC3") (pin "7") (pinfunction "OUT_7") (pintype "output"))
    )
    (net (code "48") (name "Net-(F4-1-Pad2)") (class "Default")
      (node (ref "F4") (pin "1") (pinfunction "1_1") (pintype "passive"))
      (node (ref "F4") (pin "2") (pinfunction "1_2") (pintype "passive"))
      (node (ref "TR1") (pin "3") (pinfunction "3_3") (pintype "passive"))
      (node (ref "TR1") (pin "5") (pinfunction "5_5") (pintype "passive"))
    )
    (net (code "49") (name "Net-(FAN-Pad2)") (class "Default")
      (node (ref "FAN") (pin "2") (pinfunction "2_2") (pintype "passive"))
      (node (ref "R13") (pin "1") (pinfunction "1_1") (pintype "passive"))
    )
    (net (code "50") (name "Net-(IC1-ADJ)") (class "Default")
      (node (ref "IC1") (pin "1") (pinfunction "ADJ_1") (pintype "input"))
      (node (ref "R2") (pin "2") (pinfunction "2_2") (pintype "passive"))
      (node (ref "R3") (pin "1") (pinfunction "1_1") (pintype "passive"))
    )
    (net (code "51") (name "Net-(IC2-RS-)") (class "Default")
      (node (ref "C5") (pin "1") (pinfunction "1_1") (pintype "passive"))
      (node (ref "D4") (pin "C") (pinfunction "C_C") (pintype "passive"))
      (node (ref "IC2") (pin "8") (pinfunction "RS-_8") (pintype "input"))
      (node (ref "R23") (pin "2") (pinfunction "2_2") (pintype "passive"))
      (node (ref "T1") (pin "2") (pinfunction "C_2") (pintype "passive"))
      (node (ref "T4") (pin "C") (pinfunction "C_C") (pintype "passive"))
    )
    (net (code "52") (name "Net-(IC3A--IN)") (class "Default")
      (node (ref "C12") (pin "1") (pinfunction "1_1") (pintype "passive"))
      (node (ref "IC3") (pin "2") (pinfunction "-IN_2") (pintype "input"))
      (node (ref "R10") (pin "2") (pinfunction "2_2") (pintype "passive"))
      (node (ref "R8") (pin "2") (pinfunction "2_2") (pintype "passive"))
      (node (ref "R9") (pin "1") (pinfunction "1_1") (pintype "passive"))
    )
    (net (code "53") (name "Net-(IC3A-OUT)") (class "Default")
      (node (ref "C12") (pin "2") (pinfunction "2_2") (pintype "passive"))
      (node (ref "IC3") (pin "1") (pinfunction "OUT_1") (pintype "output"))
      (node (ref "R6") (pin "2") (pinfunction "2_2") (pintype "passive"))
    )
    (net (code "54") (name "Net-(IC3C--IN)") (class "Default")
      (node (ref "IC3") (pin "9") (pinfunction "-IN_9") (pintype "input"))
      (node (ref "R18") (pin "1") (pinfunction "1_1") (pintype "passive"))
      (node (ref "R19") (pin "1") (pinfunction "1_1") (pintype "passive"))
      (node (ref "T3") (pin "E") (pinfunction "E_E") (pintype "passive"))
    )
    (net (code "55") (name "Net-(IC3C-OUT)") (class "Default")
      (node (ref "IC3") (pin "8") (pinfunction "OUT_8") (pintype "output"))
      (node (ref "T3") (pin "B") (pinfunction "B_B") (pintype "passive"))
    )
    (net (code "56") (name "Net-(IC3D--IN)") (class "Default")
      (node (ref "IC3") (pin "13") (pinfunction "-IN_13") (pintype "input"))
      (node (ref "IC3") (pin "14") (pinfunction "OUT_14") (pintype "output"))
      (node (ref "R20") (pin "1") (pinfunction "1_1") (pintype "passive"))
    )
    (net (code "57") (name "Net-(IC9A-+IN)") (class "Default")
      (node (ref "C23") (pin "1") (pinfunction "1_1") (pintype "passive"))
      (node (ref "IC9") (pin "3") (pinfunction "+IN_3") (pintype "input"))
      (node (ref "R14") (pin "2") (pinfunction "2_2") (pintype "passive"))
      (node (ref "R15") (pin "1") (pinfunction "1_1") (pintype "passive"))
    )
    (net (code "58") (name "Net-(IC9A--IN)") (class "Default")
      (node (ref "IC9") (pin "2") (pinfunction "-IN_2") (pintype "input"))
      (node (ref "R16") (pin "1") (pinfunction "1_1") (pintype "passive"))
      (node (ref "R17") (pin "1") (pinfunction "1_1") (pintype "passive"))
      (node (ref "T2") (pin "E") (pinfunction "E_E") (pintype "passive"))
    )
    (net (code "59") (name "Net-(IC9A-OUT)") (class "Default")
      (node (ref "IC9") (pin "1") (pinfunction "OUT_1") (pintype "output"))
      (node (ref "R22") (pin "1") (pinfunction "1_1") (pintype "passive"))
    )
    (net (code "60") (name "Net-(IC9B-+IN)") (class "Default")
      (node (ref "IC9") (pin "5") (pinfunction "+IN_5") (pintype "input"))
      (node (ref "R28") (pin "2") (pinfunction "2_2") (pintype "passive"))
      (node (ref "R29") (pin "1") (pinfunction "1_1") (pintype "passive"))
    )
    (net (code "61") (name "Net-(IC9B--IN)") (class "Default")
      (node (ref "C18") (pin "2") (pinfunction "2_2") (pintype "passive"))
      (node (ref "IC9") (pin "6") (pinfunction "-IN_6") (pintype "input"))
      (node (ref "R30") (pin "2") (pinfunction "2_2") (pintype "passive"))
    )
    (net (code "62") (name "Net-(IC9B-OUT)") (class "Default")
      (node (ref "C18") (pin "1") (pinfunction "1_1") (pintype "passive"))
      (node (ref "IC9") (pin "7") (pinfunction "OUT_7") (pintype "output"))
      (node (ref "T5") (pin "1") (pinfunction "G_1") (pintype "passive"))
    )
    (net (code "63") (name "Net-(R22-Pad2)") (class "Default")
      (node (ref "R22") (pin "2") (pinfunction "2_2") (pintype "passive"))
      (node (ref "T2") (pin "B") (pinfunction "B_B") (pintype "passive"))
    )
    (net (code "64") (name "Net-(T1-E)") (class "Default")
      (node (ref "T1") (pin "1") (pinfunction "E_1") (pintype "passive"))
      (node (ref "T4") (pin "B") (pinfunction "B_B") (pintype "passive"))
    )
    (net (code "65") (name "Net-(T5-S)") (class "Default")
      (node (ref "R30") (pin "1") (pinfunction "1_1") (pintype "passive"))
      (node (ref "R31") (pin "1") (pinfunction "1_1") (pintype "passive"))
      (node (ref "T5") (pin "2") (pinfunction "S_2") (pintype "passive"))
    )
    (net (code "66") (name "Net-(T6-D)") (class "Default")
      (node (ref "D1") (pin "A") (pinfunction "A_A") (pintype "passive"))
      (node (ref "REL1") (pin "-") (pinfunction "-_-") (pintype "passive"))
      (node (ref "T6") (pin "3") (pinfunction "D_3") (pintype "passive"))
    )
    (net (code "67") (name "Net-(TR2-S3)") (class "Default")
      (node (ref "F2") (pin "1") (pinfunction "1_1") (pintype "passive"))
      (node (ref "F2") (pin "2") (pinfunction "1_2") (pintype "passive"))
      (node (ref "TR2") (pin "3") (pinfunction "S3_3") (pintype "passive"))
    )
    (net (code "68") (name "Net-(TR2-S4)") (class "Default")
      (node (ref "BR1") (pin "AC2") (pinfunction "AC2_AC2") (pintype "passive"))
      (node (ref "TR2") (pin "4") (pinfunction "S4_4") (pintype "passive"))
    )
    (net (code "69") (name "Net-(U1-XTAL1)") (class "Default")
      (node (ref "C15") (pin "2") (pinfunction "2_2") (pintype "passive"))
      (node (ref "Q1") (pin "1") (pinfunction "1_1") (pintype "passive"))
      (node (ref "U1") (pin "8") (pinfunction "XTAL1_8") (pintype "bidirectional"))
    )
    (net (code "70") (name "Net-(U1-XTAL2)") (class "Default")
      (node (ref "C14") (pin "2") (pinfunction "2_2") (pintype "passive"))
      (node (ref "Q1") (pin "2") (pinfunction "2_2") (pintype "passive"))
      (node (ref "U1") (pin "7") (pinfunction "XTAL2_7") (pintype "bidirectional"))
    )
    (net (code "71") (name "P_VSS") (class "Default")
      (node (ref "BR1") (pin "-") (pinfunction "DC-_-") (pintype "passive"))
      (node (ref "BR2") (pin "DC-") (pinfunction "DC-_DC-") (pintype "passive"))
      (node (ref "C1") (pin "-") (pinfunction "-_-") (pintype "passive"))
      (node (ref "C10") (pin "-") (pinfunction "-_-") (pintype "passive"))
      (node (ref "C2") (pin "1") (pinfunction "1_1") (pintype "passive"))
      (node (ref "C27") (pin "-") (pinfunction "-_-") (pintype "passive"))
      (node (ref "C3") (pin "-") (pinfunction "-_-") (pintype "passive"))
      (node (ref "C5") (pin "2") (pinfunction "2_2") (pintype "passive"))
      (node (ref "C6") (pin "2") (pinfunction "2_2") (pintype "passive"))
      (node (ref "C7") (pin "2") (pinfunction "2_2") (pintype "passive"))
      (node (ref "C9") (pin "2") (pinfunction "2_2") (pintype "passive"))
      (node (ref "D5") (pin "A") (pinfunction "A_A") (pintype "passive"))
      (node (ref "FAN") (pin "1") (pinfunction "1_1") (pintype "passive"))
      (node (ref "HS1") (pin "1") (pinfunction "1_1") (pintype "passive"))
      (node (ref "HS1") (pin "2") (pinfunction "2_2") (pintype "passive"))
      (node (ref "IC4") (pin "2") (pinfunction "GND_2") (pintype "passive"))
      (node (ref "R3") (pin "2") (pinfunction "2_2") (pintype "passive"))
      (node (ref "REL1") (pin "O2") (pinfunction "O_O2") (pintype "passive"))
      (node (ref "REL1") (pin "P2") (pinfunction "P_P2") (pintype "passive"))
      (node (ref "SUPPLY") (pin "2") (pinfunction "2_2") (pintype "passive"))
      (node (ref "SUPPLY") (pin "3") (pinfunction "3_3") (pintype "passive"))
    )
    (net (code "72") (name "REL-OUT") (class "Default")
      (node (ref "R7") (pin "1") (pinfunction "1_1") (pintype "passive"))
      (node (ref "T6") (pin "1") (pinfunction "G_1") (pintype "passive"))
      (node (ref "U1") (pin "23") (pinfunction "(TDO/PCINT20)PC4_23") (pintype "bidirectional"))
    )
    (net (code "73") (name "RESET") (class "Default")
      (node (ref "ISP") (pin "5") (pinfunction "5_5") (pintype "passive"))
      (node (ref "R12") (pin "2") (pinfunction "2_2") (pintype "passive"))
      (node (ref "RESET") (pin "1") (pinfunction "1_1") (pintype "passive"))
      (node (ref "SERIAL") (pin "4") (pinfunction "4_4") (pintype "passive"))
      (node (ref "U1") (pin "4") (pinfunction "~{RESET}_4") (pintype "bidirectional"))
    )
    (net (code "74") (name "RX") (class "Default")
      (node (ref "SERIAL") (pin "2") (pinfunction "2_2") (pintype "passive"))
      (node (ref "U1") (pin "9") (pinfunction "PD0(PCINT24/RXD0)_9") (pintype "bidirectional"))
    )
    (net (code "75") (name "SCK") (class "Default")
      (node (ref "IC8") (pin "4") (pinfunction "SCK_4") (pintype "input"))
      (node (ref "ISP") (pin "3") (pinfunction "3_3") (pintype "passive"))
      (node (ref "U1") (pin "3") (pinfunction "PB7(PCINT15/SCK)_3") (pintype "bidirectional"))
    )
    (net (code "76") (name "TX") (class "Default")
      (node (ref "SERIAL") (pin "1") (pinfunction "1_1") (pintype "passive"))
      (node (ref "U1") (pin "10") (pinfunction "PD1(PCINT25/TXD0)_10") (pintype "bidirectional"))
    )
    (net (code "77") (name "VREF4096") (class "Default")
      (node (ref "C17") (pin "1") (pinfunction "1_1") (pintype "passive"))
      (node (ref "C20") (pin "+") (pinfunction "+_+") (pintype "passive"))
      (node (ref "IC7") (pin "2") (pinfunction "VOUT_2") (pintype "output"))
      (node (ref "IC8") (pin "11") (pinfunction "VREFB_11") (pintype "input"))
      (node (ref "IC8") (pin "13") (pinfunction "VREFA_13") (pintype "input"))
      (node (ref "U1") (pin "29") (pinfunction "AREF_29") (pintype "bidirectional"))
    )
    (net (code "78") (name "VSET") (class "Default")
      (node (ref "IC3") (pin "3") (pinfunction "+IN_3") (pintype "input"))
      (node (ref "IC8") (pin "10") (pinfunction "VOUTB_10") (pintype "output"))
    )
    (net (code "79") (name "VSS") (class "Default")
      (node (ref "5V") (pin "1") (pinfunction "1_1") (pintype "passive"))
      (node (ref "C14") (pin "1") (pinfunction "1_1") (pintype "passive"))
      (node (ref "C15") (pin "1") (pinfunction "1_1") (pintype "passive"))
      (node (ref "C32") (pin "2") (pinfunction "2_2") (pintype "passive"))
      (node (ref "C33") (pin "2") (pinfunction "2_2") (pintype "passive"))
      (node (ref "C34") (pin "2") (pinfunction "2_2") (pintype "passive"))
      (node (ref "ISP") (pin "6") (pinfunction "6_6") (pintype "passive"))
      (node (ref "PANEL") (pin "14") (pinfunction "14_14") (pintype "passive"))
      (node (ref "PANEL") (pin "5") (pinfunction "5_5") (pintype "passive"))
      (node (ref "PANEL") (pin "6") (pinfunction "6_6") (pintype "passive"))
      (node (ref "RESET") (pin "3") (pinfunction "2_3") (pintype "passive"))
      (node (ref "SERIAL") (pin "3") (pinfunction "3_3") (pintype "passive"))
      (node (ref "T6") (pin "2") (pinfunction "S_2") (pintype "passive"))
      (node (ref "U1") (pin "18") (pinfunction "GND_18") (pintype "bidirectional"))
      (node (ref "U1") (pin "28") (pinfunction "GND_28") (pintype "bidirectional"))
      (node (ref "U1") (pin "39") (pinfunction "GND_39") (pintype "bidirectional"))
      (node (ref "U1") (pin "6") (pinfunction "GND_6") (pintype "bidirectional"))
    )
    (net (code "80") (name "V_OUT_CONN") (class "Default")
      (node (ref "OUT") (pin "2") (pinfunction "2_2") (pintype "passive"))
      (node (ref "REL1") (pin "S1") (pinfunction "S_S1") (pintype "passive"))
    )
    (net (code "81") (name "unconnected-(U1-(ADC1{slash}PINT1)PA1-Pad36)") (class "Default")
      (node (ref "U1") (pin "36") (pinfunction "(ADC1/PINT1)PA1_36") (pintype "bidirectional"))
    )
    (net (code "82") (name "unconnected-(U1-(ADC2{slash}PINT2)PA2-Pad35)") (class "Default")
      (node (ref "U1") (pin "35") (pinfunction "(ADC2/PINT2)PA2_35") (pintype "bidirectional"))
    )
    (net (code "83") (name "unconnected-(U1-(ADC3{slash}PINT3)PA3-Pad34)") (class "Default")
      (node (ref "U1") (pin "34") (pinfunction "(ADC3/PINT3)PA3_34") (pintype "bidirectional"))
    )
    (net (code "84") (name "unconnected-(U1-(ADC7{slash}PINT7)PA7-Pad30)") (class "Default")
      (node (ref "U1") (pin "30") (pinfunction "(ADC7/PINT7)PA7_30") (pintype "bidirectional"))
    )
    (net (code "85") (name "unconnected-(U1-(SS{slash}OC0B{slash}PCINT12)PB4-Pad44)") (class "Default")
      (node (ref "U1") (pin "44") (pinfunction "(SS/OC0B/PCINT12)PB4_44") (pintype "bidirectional"))
    )
    (net (code "86") (name "unconnected-(U1-PD2(PCINT26{slash}INT0)-Pad11)") (class "Default")
      (node (ref "U1") (pin "11") (pinfunction "PD2(PCINT26/INT0)_11") (pintype "bidirectional"))
    )
  )
)
